# LedPanel.net
KiCad netlist of a schematic drawn in EAGLE
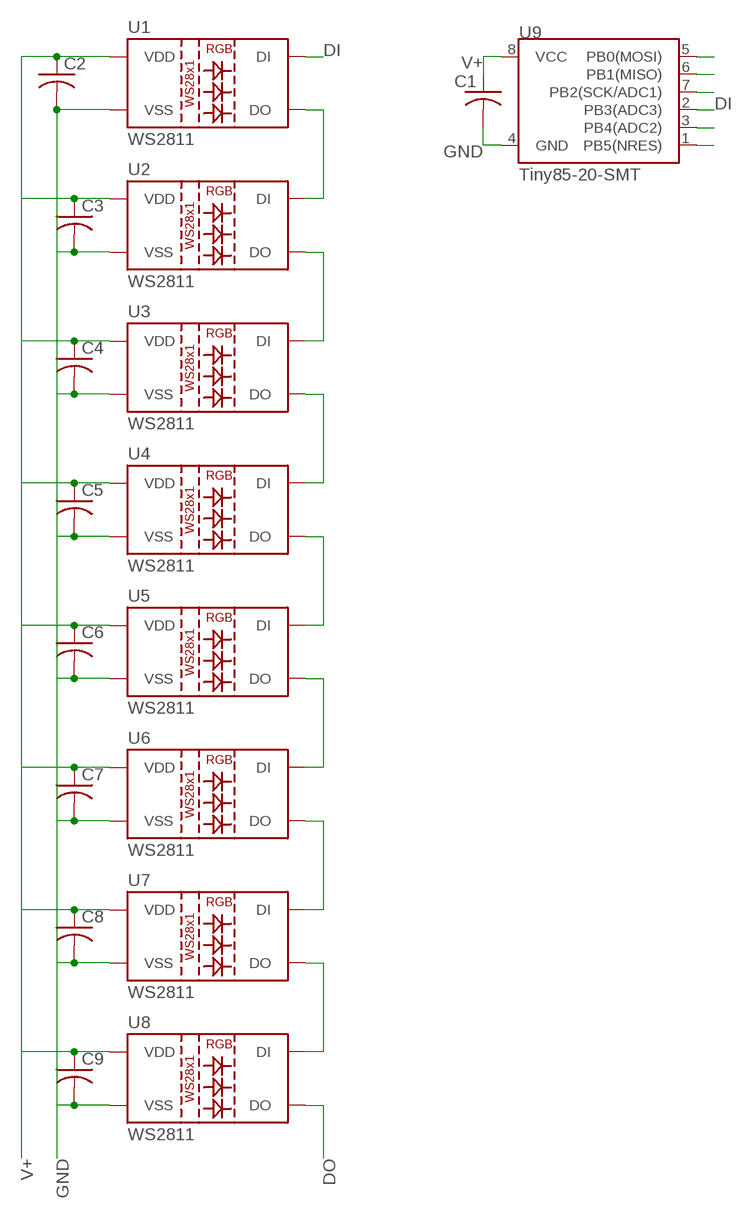
[diagram p0: schematic, sheet 1]

(export (version "E")
  (design (tool "Eeschema 10.0.6"))
  (components
    (comp (ref "C1")
      (value "C-USC0805")
      (footprint "eagle-import:C0805")
      (libsource (lib "eagle-import") (part "C-USC0805"))
    )
    (comp (ref "C2")
      (value "C-USC0805")
      (footprint "eagle-import:C0805")
      (libsource (lib "eagle-import") (part "C-USC0805"))
    )
    (comp (ref "C3")
      (value "C-USC0805")
      (footprint "eagle-import:C0805")
      (libsource (lib "eagle-import") (part "C-USC0805"))
    )
    (comp (ref "C4")
      (value "C-USC0805")
      (footprint "eagle-import:C0805")
      (libsource (lib "eagle-import") (part "C-USC0805"))
    )
    (comp (ref "C5")
      (value "C-USC0805")
      (footprint "eagle-import:C0805")
      (libsource (lib "eagle-import") (part "C-USC0805"))
    )
    (comp (ref "C6")
      (value "C-USC0805")
      (footprint "eagle-import:C0805")
      (libsource (lib "eagle-import") (part "C-USC0805"))
    )
    (comp (ref "C7")
      (value "C-USC0805")
      (footprint "eagle-import:C0805")
      (libsource (lib "eagle-import") (part "C-USC0805"))
    )
    (comp (ref "C8")
      (value "C-USC0805")
      (footprint "eagle-import:C0805")
      (libsource (lib "eagle-import") (part "C-USC0805"))
    )
    (comp (ref "C9")
      (value "C-USC0805")
      (footprint "eagle-import:C0805")
      (libsource (lib "eagle-import") (part "C-USC0805"))
    )
    (comp (ref "U1")
      (value "WS2811")
      (footprint "eagle-import:LED-TRICOLOR-5050-IC")
      (libsource (lib "eagle-import") (part "LED-TRICOLOR-5050-ICWS2811"))
    )
    (comp (ref "U2")
      (value "WS2811")
      (footprint "eagle-import:LED-TRICOLOR-5050-IC")
      (libsource (lib "eagle-import") (part "LED-TRICOLOR-5050-ICWS2811"))
    )
    (comp (ref "U3")
      (value "WS2811")
      (footprint "eagle-import:LED-TRICOLOR-5050-IC")
      (libsource (lib "eagle-import") (part "LED-TRICOLOR-5050-ICWS2811"))
    )
    (comp (ref "U4")
      (value "WS2811")
      (footprint "eagle-import:LED-TRICOLOR-5050-IC")
      (libsource (lib "eagle-import") (part "LED-TRICOLOR-5050-ICWS2811"))
    )
    (comp (ref "U5")
      (value "WS2811")
      (footprint "eagle-import:LED-TRICOLOR-5050-IC")
      (libsource (lib "eagle-import") (part "LED-TRICOLOR-5050-ICWS2811"))
    )
    (comp (ref "U6")
      (value "WS2811")
      (footprint "eagle-import:LED-TRICOLOR-5050-IC")
      (libsource (lib "eagle-import") (part "LED-TRICOLOR-5050-ICWS2811"))
    )
    (comp (ref "U7")
      (value "WS2811")
      (footprint "eagle-import:LED-TRICOLOR-5050-IC")
      (libsource (lib "eagle-import") (part "LED-TRICOLOR-5050-ICWS2811"))
    )
    (comp (ref "U8")
      (value "WS2811")
      (footprint "eagle-import:LED-TRICOLOR-5050-IC")
      (libsource (lib "eagle-import") (part "LED-TRICOLOR-5050-ICWS2811"))
    )
    (comp (ref "U9")
      (value "Tiny85-20-SMT")
      (footprint "eagle-import:SO08-EIAJ")
      (libsource (lib "eagle-import") (part "ATTINY45TINY85-20-SMT"))
    )
  )
  (nets
    (net (code "1") (name "/DI") (class "Default")
      (node (ref "U1") (pin "2") (pinfunction "DI_2") (pintype "bidirectional"))
      (node (ref "U9") (pin "2") (pinfunction "PB3(ADC3)_2") (pintype "bidirectional"))
    )
    (net (code "2") (name "/DO") (class "Default")
      (node (ref "U8") (pin "1") (pinfunction "DO_1") (pintype "bidirectional"))
    )
    (net (code "3") (name "/GND") (class "Default")
      (node (ref "C1") (pin "2") (pinfunction "2_2") (pintype "passive"))
      (node (ref "C2") (pin "2") (pinfunction "2_2") (pintype "passive"))
      (node (ref "C3") (pin "2") (pinfunction "2_2") (pintype "passive"))
      (node (ref "C4") (pin "2") (pinfunction "2_2") (pintype "passive"))
      (node (ref "C5") (pin "2") (pinfunction "2_2") (pintype "passive"))
      (node (ref "C6") (pin "2") (pinfunction "2_2") (pintype "passive"))
      (node (ref "C7") (pin "2") (pinfunction "2_2") (pintype "passive"))
      (node (ref "C8") (pin "2") (pinfunction "2_2") (pintype "passive"))
      (node (ref "C9") (pin "2") (pinfunction "2_2") (pintype "passive"))
      (node (ref "U1") (pin "6") (pinfunction "VSS_6") (pintype "bidirectional"))
      (node (ref "U2") (pin "6") (pinfunction "VSS_6") (pintype "bidirectional"))
      (node (ref "U3") (pin "6") (pinfunction "VSS_6") (pintype "bidirectional"))
      (node (ref "U4") (pin "6") (pinfunction "VSS_6") (pintype "bidirectional"))
      (node (ref "U5") (pin "6") (pinfunction "VSS_6") (pintype "bidirectional"))
      (node (ref "U6") (pin "6") (pinfunction "VSS_6") (pintype "bidirectional"))
      (node (ref "U7") (pin "6") (pinfunction "VSS_6") (pintype "bidirectional"))
      (node (ref "U8") (pin "6") (pinfunction "VSS_6") (pintype "bidirectional"))
      (node (ref "U9") (pin "4") (pinfunction "GND_4") (pintype "bidirectional"))
    )
    (net (code "4") (name "/V+") (class "Default")
      (node (ref "C1") (pin "1") (pinfunction "1_1") (pintype "passive"))
      (node (ref "C2") (pin "1") (pinfunction "1_1") (pintype "passive"))
      (node (ref "C3") (pin "1") (pinfunction "1_1") (pintype "passive"))
      (node (ref "C4") (pin "1") (pinfunction "1_1") (pintype "passive"))
      (node (ref "C5") (pin "1") (pinfunction "1_1") (pintype "passive"))
      (node (ref "C6") (pin "1") (pinfunction "1_1") (pintype "passive"))
      (node (ref "C7") (pin "1") (pinfunction "1_1") (pintype "passive"))
      (node (ref "C8") (pin "1") (pinfunction "1_1") (pintype "passive"))
      (node (ref "C9") (pin "1") (pinfunction "1_1") (pintype "passive"))
      (node (ref "U1") (pin "3") (pinfunction "VDD_3") (pintype "bidirectional"))
      (node (ref "U1") (pin "5") (pinfunction "VDD_5") (pintype "bidirectional"))
      (node (ref "U2") (pin "3") (pinfunction "VDD_3") (pintype "bidirectional"))
      (node (ref "U2") (pin "5") (pinfunction "VDD_5") (pintype "bidirectional"))
      (node (ref "U3") (pin "3") (pinfunction "VDD_3") (pintype "bidirectional"))
      (node (ref "U3") (pin "5") (pinfunction "VDD_5") (pintype "bidirectional"))
      (node (ref "U4") (pin "3") (pinfunction "VDD_3") (pintype "bidirectional"))
      (node (ref "U4") (pin "5") (pinfunction "VDD_5") (pintype "bidirectional"))
      (node (ref "U5") (pin "3") (pinfunction "VDD_3") (pintype "bidirectional"))
      (node (ref "U5") (pin "5") (pinfunction "VDD_5") (pintype "bidirectional"))
      (node (ref "U6") (pin "3") (pinfunction "VDD_3") (pintype "bidirectional"))
      (node (ref "U6") (pin "5") (pinfunction "VDD_5") (pintype "bidirectional"))
      (node (ref "U7") (pin "3") (pinfunction "VDD_3") (pintype "bidirectional"))
      (node (ref "U7") (pin "5") (pinfunction "VDD_5") (pintype "bidirectional"))
      (node (ref "U8") (pin "3") (pinfunction "VDD_3") (pintype "bidirectional"))
      (node (ref "U8") (pin "5") (pinfunction "VDD_5") (pintype "bidirectional"))
      (node (ref "U9") (pin "8") (pinfunction "VCC_8") (pintype "bidirectional"))
    )
    (net (code "5") (name "Net-(U1-DO)") (class "Default")
      (node (ref "U1") (pin "1") (pinfunction "DO_1") (pintype "bidirectional"))
      (node (ref "U2") (pin "2") (pinfunction "DI_2") (pintype "bidirectional"))
    )
    (net (code "6") (name "Net-(U2-DO)") (class "Default")
      (node (ref "U2") (pin "1") (pinfunction "DO_1") (pintype "bidirectional"))
      (node (ref "U3") (pin "2") (pinfunction "DI_2") (pintype "bidirectional"))
    )
    (net (code "7") (name "Net-(U3-DO)") (class "Default")
      (node (ref "U3") (pin "1") (pinfunction "DO_1") (pintype "bidirectional"))
      (node (ref "U4") (pin "2") (pinfunction "DI_2") (pintype "bidirectional"))
    )
    (net (code "8") (name "Net-(U4-DO)") (class "Default")
      (node (ref "U4") (pin "1") (pinfunction "DO_1") (pintype "bidirectional"))
      (node (ref "U5") (pin "2") (pinfunction "DI_2") (pintype "bidirectional"))
    )
    (net (code "9") (name "Net-(U5-DO)") (class "Default")
      (node (ref "U5") (pin "1") (pinfunction "DO_1") (pintype "bidirectional"))
      (node (ref "U6") (pin "2") (pinfunction "DI_2") (pintype "bidirectional"))
    )
    (net (code "10") (name "Net-(U6-DO)") (class "Default")
      (node (ref "U6") (pin "1") (pinfunction "DO_1") (pintype "bidirectional"))
      (node (ref "U7") (pin "2") (pinfunction "DI_2") (pintype "bidirectional"))
    )
    (net (code "11") (name "Net-(U7-DO)") (class "Default")
      (node (ref "U7") (pin "1") (pinfunction "DO_1") (pintype "bidirectional"))
      (node (ref "U8") (pin "2") (pinfunction "DI_2") (pintype "bidirectional"))
    )
    (net (code "12") (name "unconnected-(U9-PB0(MOSI)-Pad5)") (class "Default")
      (node (ref "U9") (pin "5") (pinfunction "PB0(MOSI)_5") (pintype "bidirectional"))
    )
    (net (code "13") (name "unconnected-(U9-PB1(MISO)-Pad6)") (class "Default")
      (node (ref "U9") (pin "6") (pinfunction "PB1(MISO)_6") (pintype "bidirectional"))
    )
    (net (code "14") (name "unconnected-(U9-PB2(SCK{slash}ADC1)-Pad7)") (class "Default")
      (node (ref "U9") (pin "7") (pinfunction "PB2(SCK/ADC1)_7") (pintype "bidirectional"))
    )
    (net (code "15") (name "unconnected-(U9-PB4(ADC2)-Pad3)") (class "Default")
      (node (ref "U9") (pin "3") (pinfunction "PB4(ADC2)_3") (pintype "bidirectional"))
    )
    (net (code "16") (name "unconnected-(U9-PB5(NRES)-Pad1)") (class "Default")
      (node (ref "U9") (pin "1") (pinfunction "PB5(NRES)_1") (pintype "bidirectional"))
    )
  )
)
